# rev1.net
KiCad netlist of a schematic drawn in EAGLE
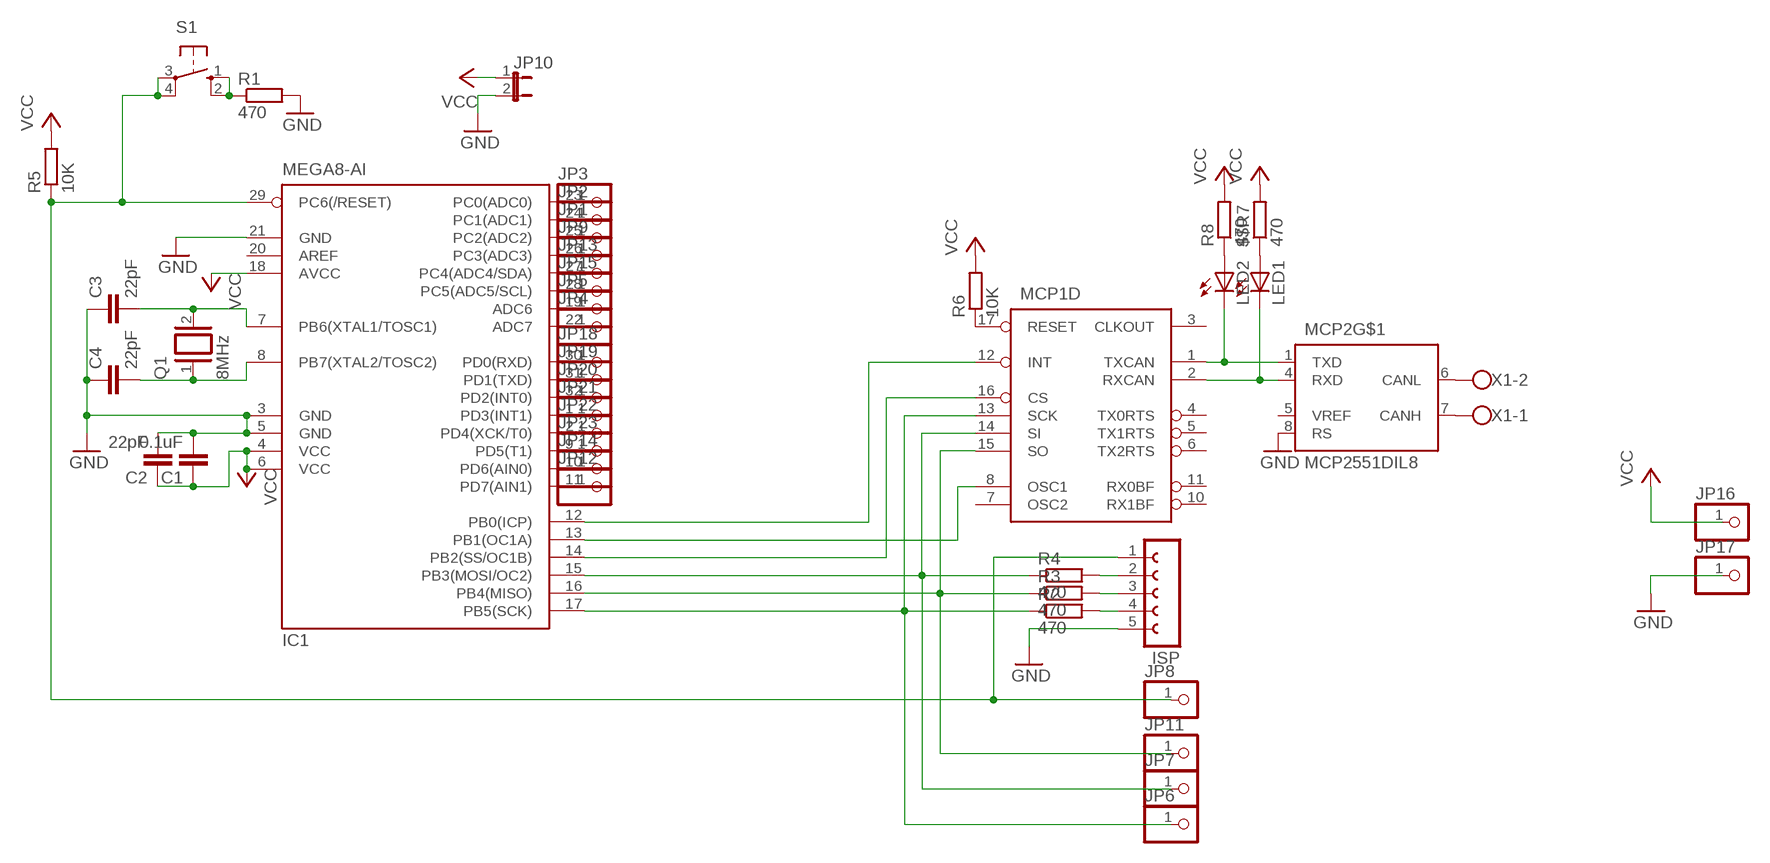
[diagram p0: schematic, sheet 1]

(export (version "E")
  (design (tool "Eeschema 10.0.6"))
  (components
    (comp (ref "$$R7")
      (value "470")
      (footprint "eagle-import:R0603")
      (libsource (lib "eagle-import") (part "R-EU_R0603"))
    )
    (comp (ref "C1")
      (value "0.1uF")
      (footprint "eagle-import:C0603")
      (libsource (lib "eagle-import") (part "C-EUC0603"))
    )
    (comp (ref "C2")
      (value "22pF")
      (footprint "eagle-import:C0603")
      (libsource (lib "eagle-import") (part "C-EUC0603"))
    )
    (comp (ref "C3")
      (value "22pF")
      (footprint "eagle-import:C0603")
      (libsource (lib "eagle-import") (part "C-EUC0603"))
    )
    (comp (ref "C4")
      (value "22pF")
      (footprint "eagle-import:C0603")
      (libsource (lib "eagle-import") (part "C-EUC0603"))
    )
    (comp (ref "IC1")
      (value "MEGA8-AI")
      (footprint "eagle-import:TQFP32-08")
      (fields (field (name "MPN") "ATMEGA8-16AU") (field (name "OC_NEWARK") "unknown"))
      (libsource (lib "eagle-import") (part "MEGA8-AI"))
    )
    (comp (ref "ISP")
      (value "FE05-1")
      (footprint "eagle-import:FE05-1")
      (libsource (lib "eagle-import") (part "FE05-1"))
    )
    (comp (ref "JP1")
      (value "PINHD-1X1")
      (footprint "eagle-import:1X01")
      (libsource (lib "eagle-import") (part "PINHD-1X1"))
    )
    (comp (ref "JP2")
      (value "PINHD-1X1")
      (footprint "eagle-import:1X01")
      (libsource (lib "eagle-import") (part "PINHD-1X1"))
    )
    (comp (ref "JP3")
      (value "PINHD-1X1")
      (footprint "eagle-import:1X01")
      (libsource (lib "eagle-import") (part "PINHD-1X1"))
    )
    (comp (ref "JP4")
      (value "PINHD-1X1")
      (footprint "eagle-import:1X01")
      (libsource (lib "eagle-import") (part "PINHD-1X1"))
    )
    (comp (ref "JP5")
      (value "PINHD-1X1")
      (footprint "eagle-import:1X01")
      (libsource (lib "eagle-import") (part "PINHD-1X1"))
    )
    (comp (ref "JP6")
      (value "PINHD-1X1")
      (footprint "eagle-import:1X01")
      (libsource (lib "eagle-import") (part "PINHD-1X1"))
    )
    (comp (ref "JP7")
      (value "PINHD-1X1")
      (footprint "eagle-import:1X01")
      (libsource (lib "eagle-import") (part "PINHD-1X1"))
    )
    (comp (ref "JP8")
      (value "PINHD-1X1")
      (footprint "eagle-import:1X01")
      (libsource (lib "eagle-import") (part "PINHD-1X1"))
    )
    (comp (ref "JP9")
      (value "PINHD-1X1")
      (footprint "eagle-import:1X01")
      (libsource (lib "eagle-import") (part "PINHD-1X1"))
    )
    (comp (ref "JP10")
      (value "JUMPER-2PTH")
      (footprint "eagle-import:1X02")
      (libsource (lib "eagle-import") (part "JUMPER-2PTH"))
    )
    (comp (ref "JP11")
      (value "PINHD-1X1")
      (footprint "eagle-import:1X01")
      (libsource (lib "eagle-import") (part "PINHD-1X1"))
    )
    (comp (ref "JP12")
      (value "PINHD-1X1")
      (footprint "eagle-import:1X01")
      (libsource (lib "eagle-import") (part "PINHD-1X1"))
    )
    (comp (ref "JP13")
      (value "PINHD-1X1")
      (footprint "eagle-import:1X01")
      (libsource (lib "eagle-import") (part "PINHD-1X1"))
    )
    (comp (ref "JP14")
      (value "PINHD-1X1")
      (footprint "eagle-import:1X01")
      (libsource (lib "eagle-import") (part "PINHD-1X1"))
    )
    (comp (ref "JP15")
      (value "PINHD-1X1")
      (footprint "eagle-import:1X01")
      (libsource (lib "eagle-import") (part "PINHD-1X1"))
    )
    (comp (ref "JP16")
      (value "PINHD-1X1")
      (footprint "eagle-import:1X01")
      (libsource (lib "eagle-import") (part "PINHD-1X1"))
    )
    (comp (ref "JP17")
      (value "PINHD-1X1")
      (footprint "eagle-import:1X01")
      (libsource (lib "eagle-import") (part "PINHD-1X1"))
    )
    (comp (ref "JP18")
      (value "PINHD-1X1")
      (footprint "eagle-import:1X01")
      (libsource (lib "eagle-import") (part "PINHD-1X1"))
    )
    (comp (ref "JP19")
      (value "PINHD-1X1")
      (footprint "eagle-import:1X01")
      (libsource (lib "eagle-import") (part "PINHD-1X1"))
    )
    (comp (ref "JP20")
      (value "PINHD-1X1")
      (footprint "eagle-import:1X01")
      (libsource (lib "eagle-import") (part "PINHD-1X1"))
    )
    (comp (ref "JP21")
      (value "PINHD-1X1")
      (footprint "eagle-import:1X01")
      (libsource (lib "eagle-import") (part "PINHD-1X1"))
    )
    (comp (ref "JP22")
      (value "PINHD-1X1")
      (footprint "eagle-import:1X01")
      (libsource (lib "eagle-import") (part "PINHD-1X1"))
    )
    (comp (ref "JP23")
      (value "PINHD-1X1")
      (footprint "eagle-import:1X01")
      (libsource (lib "eagle-import") (part "PINHD-1X1"))
    )
    (comp (ref "LED1")
      (value "LEDCHIP-LED0603")
      (footprint "eagle-import:CHIP-LED0603")
      (libsource (lib "eagle-import") (part "LEDCHIP-LED0603"))
    )
    (comp (ref "LED2")
      (value "LEDCHIP-LED0603")
      (footprint "eagle-import:CHIP-LED0603")
      (libsource (lib "eagle-import") (part "LEDCHIP-LED0603"))
    )
    (comp (ref "MCP1")
      (value "MCP2515P")
      (footprint "eagle-import:DIL18")
      (libsource (lib "eagle-import") (part "MCP2515P"))
    )
    (comp (ref "MCP2")
      (value "MCP2551DIL8")
      (footprint "eagle-import:DIL08")
      (libsource (lib "eagle-import") (part "MCP2551DIL8"))
    )
    (comp (ref "Q1")
      (value "8MHz")
      (footprint "eagle-import:QS")
      (libsource (lib "eagle-import") (part "XTAL/S"))
    )
    (comp (ref "R1")
      (value "470")
      (footprint "eagle-import:R0603")
      (libsource (lib "eagle-import") (part "R-EU_R0603"))
    )
    (comp (ref "R2")
      (value "470")
      (footprint "eagle-import:R0603")
      (libsource (lib "eagle-import") (part "R-EU_R0603"))
    )
    (comp (ref "R3")
      (value "470")
      (footprint "eagle-import:R0603")
      (libsource (lib "eagle-import") (part "R-EU_R0603"))
    )
    (comp (ref "R4")
      (value "470")
      (footprint "eagle-import:R0603")
      (libsource (lib "eagle-import") (part "R-EU_R0603"))
    )
    (comp (ref "R5")
      (value "10K")
      (footprint "eagle-import:R0603")
      (libsource (lib "eagle-import") (part "R-EU_R0603"))
    )
    (comp (ref "R6")
      (value "10K")
      (footprint "eagle-import:R0603")
      (libsource (lib "eagle-import") (part "R-EU_R0603"))
    )
    (comp (ref "R8")
      (value "470")
      (footprint "eagle-import:R0603")
      (libsource (lib "eagle-import") (part "R-EU_R0603"))
    )
    (comp (ref "S1")
      (value "10-XX")
      (footprint "eagle-import:B3F-10XX")
      (fields (field (name "MPN") "B3F-1000"))
      (libsource (lib "eagle-import") (part "10-XX"))
    )
    (comp (ref "X1")
      (value "W237-102")
      (footprint "eagle-import:W237-102")
      (fields (field (name "MPN") "237-102"))
      (libsource (lib "eagle-import") (part "W237-102"))
    )
  )
  (nets
    (net (code "1") (name "GND") (class "Default")
      (node (ref "C1") (pin "2") (pinfunction "2_2") (pintype "passive"))
      (node (ref "C2") (pin "2") (pinfunction "2_2") (pintype "passive"))
      (node (ref "C3") (pin "1") (pinfunction "1_1") (pintype "passive"))
      (node (ref "C4") (pin "1") (pinfunction "1_1") (pintype "passive"))
      (node (ref "IC1") (pin "21") (pinfunction "GND_21") (pintype "power_in"))
      (node (ref "IC1") (pin "3") (pinfunction "GND_3") (pintype "power_in"))
      (node (ref "IC1") (pin "5") (pinfunction "GND_5") (pintype "power_in"))
      (node (ref "ISP") (pin "5") (pinfunction "5_5") (pintype "passive"))
      (node (ref "JP10") (pin "2") (pinfunction "2_2") (pintype "passive"))
      (node (ref "JP17") (pin "1") (pinfunction "1_1") (pintype "passive"))
      (node (ref "MCP2") (pin "8") (pinfunction "RS_8") (pintype "bidirectional"))
      (node (ref "R1") (pin "2") (pinfunction "2_2") (pintype "passive"))
    )
    (net (code "2") (name "Net-($$R7-Pad1)") (class "Default")
      (node (ref "$$R7") (pin "1") (pinfunction "1_1") (pintype "passive"))
      (node (ref "LED1") (pin "A") (pinfunction "A_A") (pintype "passive"))
    )
    (net (code "3") (name "Net-(IC1-ADC6)") (class "Default")
      (node (ref "IC1") (pin "19") (pinfunction "ADC6_19") (pintype "bidirectional"))
      (node (ref "JP5") (pin "1") (pinfunction "1_1") (pintype "passive"))
    )
    (net (code "4") (name "Net-(IC1-ADC7)") (class "Default")
      (node (ref "IC1") (pin "22") (pinfunction "ADC7_22") (pintype "bidirectional"))
      (node (ref "JP4") (pin "1") (pinfunction "1_1") (pintype "passive"))
    )
    (net (code "5") (name "Net-(IC1-PB0(ICP))") (class "Default")
      (node (ref "IC1") (pin "12") (pinfunction "PB0(ICP)_12") (pintype "bidirectional"))
      (node (ref "MCP1") (pin "12") (pinfunction "INT_12") (pintype "output"))
    )
    (net (code "6") (name "Net-(IC1-PB1(OC1A))") (class "Default")
      (node (ref "IC1") (pin "13") (pinfunction "PB1(OC1A)_13") (pintype "bidirectional"))
      (node (ref "MCP1") (pin "8") (pinfunction "OSC1_8") (pintype "input"))
    )
    (net (code "7") (name "Net-(IC1-PB2(SS{slash}OC1B))") (class "Default")
      (node (ref "IC1") (pin "14") (pinfunction "PB2(SS/OC1B)_14") (pintype "bidirectional"))
      (node (ref "MCP1") (pin "16") (pinfunction "CS_16") (pintype "input"))
    )
    (net (code "8") (name "Net-(IC1-PB3(MOSI{slash}OC2))") (class "Default")
      (node (ref "IC1") (pin "15") (pinfunction "PB3(MOSI/OC2)_15") (pintype "bidirectional"))
      (node (ref "JP7") (pin "1") (pinfunction "1_1") (pintype "passive"))
      (node (ref "MCP1") (pin "14") (pinfunction "SI_14") (pintype "input"))
      (node (ref "R4") (pin "1") (pinfunction "1_1") (pintype "passive"))
    )
    (net (code "9") (name "Net-(IC1-PB4(MISO))") (class "Default")
      (node (ref "IC1") (pin "16") (pinfunction "PB4(MISO)_16") (pintype "bidirectional"))
      (node (ref "JP11") (pin "1") (pinfunction "1_1") (pintype "passive"))
      (node (ref "MCP1") (pin "15") (pinfunction "SO_15") (pintype "output"))
      (node (ref "R3") (pin "1") (pinfunction "1_1") (pintype "passive"))
    )
    (net (code "10") (name "Net-(IC1-PB5(SCK))") (class "Default")
      (node (ref "IC1") (pin "17") (pinfunction "PB5(SCK)_17") (pintype "bidirectional"))
      (node (ref "JP6") (pin "1") (pinfunction "1_1") (pintype "passive"))
      (node (ref "MCP1") (pin "13") (pinfunction "SCK_13") (pintype "input"))
      (node (ref "R2") (pin "1") (pinfunction "1_1") (pintype "passive"))
    )
    (net (code "11") (name "Net-(IC1-PB6(XTAL1{slash}TOSC1))") (class "Default")
      (node (ref "C3") (pin "2") (pinfunction "2_2") (pintype "passive"))
      (node (ref "IC1") (pin "7") (pinfunction "PB6(XTAL1/TOSC1)_7") (pintype "bidirectional"))
      (node (ref "Q1") (pin "2") (pinfunction "2_2") (pintype "passive"))
    )
    (net (code "12") (name "Net-(IC1-PB7(XTAL2{slash}TOSC2))") (class "Default")
      (node (ref "C4") (pin "2") (pinfunction "2_2") (pintype "passive"))
      (node (ref "IC1") (pin "8") (pinfunction "PB7(XTAL2/TOSC2)_8") (pintype "bidirectional"))
      (node (ref "Q1") (pin "1") (pinfunction "1_1") (pintype "passive"))
    )
    (net (code "13") (name "Net-(IC1-PC0(ADC0))") (class "Default")
      (node (ref "IC1") (pin "23") (pinfunction "PC0(ADC0)_23") (pintype "bidirectional"))
      (node (ref "JP3") (pin "1") (pinfunction "1_1") (pintype "passive"))
    )
    (net (code "14") (name "Net-(IC1-PC1(ADC1))") (class "Default")
      (node (ref "IC1") (pin "24") (pinfunction "PC1(ADC1)_24") (pintype "bidirectional"))
      (node (ref "JP2") (pin "1") (pinfunction "1_1") (pintype "passive"))
    )
    (net (code "15") (name "Net-(IC1-PC2(ADC2))") (class "Default")
      (node (ref "IC1") (pin "25") (pinfunction "PC2(ADC2)_25") (pintype "bidirectional"))
      (node (ref "JP1") (pin "1") (pinfunction "1_1") (pintype "passive"))
    )
    (net (code "16") (name "Net-(IC1-PC3(ADC3))") (class "Default")
      (node (ref "IC1") (pin "26") (pinfunction "PC3(ADC3)_26") (pintype "bidirectional"))
      (node (ref "JP9") (pin "1") (pinfunction "1_1") (pintype "passive"))
    )
    (net (code "17") (name "Net-(IC1-PC4(ADC4{slash}SDA))") (class "Default")
      (node (ref "IC1") (pin "27") (pinfunction "PC4(ADC4/SDA)_27") (pintype "bidirectional"))
      (node (ref "JP13") (pin "1") (pinfunction "1_1") (pintype "passive"))
    )
    (net (code "18") (name "Net-(IC1-PC5(ADC5{slash}SCL))") (class "Default")
      (node (ref "IC1") (pin "28") (pinfunction "PC5(ADC5/SCL)_28") (pintype "bidirectional"))
      (node (ref "JP15") (pin "1") (pinfunction "1_1") (pintype "passive"))
    )
    (net (code "19") (name "Net-(IC1-PC6({slash}RESET))") (class "Default")
      (node (ref "IC1") (pin "29") (pinfunction "PC6(/RESET)_29") (pintype "bidirectional"))
      (node (ref "ISP") (pin "1") (pinfunction "1_1") (pintype "passive"))
      (node (ref "JP8") (pin "1") (pinfunction "1_1") (pintype "passive"))
      (node (ref "R5") (pin "1") (pinfunction "1_1") (pintype "passive"))
      (node (ref "S1") (pin "3") (pinfunction "P_3") (pintype "passive"))
      (node (ref "S1") (pin "4") (pinfunction "P1_4") (pintype "passive"))
    )
    (net (code "20") (name "Net-(IC1-PD0(RXD))") (class "Default")
      (node (ref "IC1") (pin "30") (pinfunction "PD0(RXD)_30") (pintype "bidirectional"))
      (node (ref "JP18") (pin "1") (pinfunction "1_1") (pintype "passive"))
    )
    (net (code "21") (name "Net-(IC1-PD1(TXD))") (class "Default")
      (node (ref "IC1") (pin "31") (pinfunction "PD1(TXD)_31") (pintype "bidirectional"))
      (node (ref "JP19") (pin "1") (pinfunction "1_1") (pintype "passive"))
    )
    (net (code "22") (name "Net-(IC1-PD2(INT0))") (class "Default")
      (node (ref "IC1") (pin "32") (pinfunction "PD2(INT0)_32") (pintype "bidirectional"))
      (node (ref "JP20") (pin "1") (pinfunction "1_1") (pintype "passive"))
    )
    (net (code "23") (name "Net-(IC1-PD3(INT1))") (class "Default")
      (node (ref "IC1") (pin "1") (pinfunction "PD3(INT1)_1") (pintype "bidirectional"))
      (node (ref "JP21") (pin "1") (pinfunction "1_1") (pintype "passive"))
    )
    (net (code "24") (name "Net-(IC1-PD4(XCK{slash}T0))") (class "Default")
      (node (ref "IC1") (pin "2") (pinfunction "PD4(XCK/T0)_2") (pintype "bidirectional"))
      (node (ref "JP22") (pin "1") (pinfunction "1_1") (pintype "passive"))
    )
    (net (code "25") (name "Net-(IC1-PD5(T1))") (class "Default")
      (node (ref "IC1") (pin "9") (pinfunction "PD5(T1)_9") (pintype "bidirectional"))
      (node (ref "JP23") (pin "1") (pinfunction "1_1") (pintype "passive"))
    )
    (net (code "26") (name "Net-(IC1-PD6(AIN0))") (class "Default")
      (node (ref "IC1") (pin "10") (pinfunction "PD6(AIN0)_10") (pintype "bidirectional"))
      (node (ref "JP14") (pin "1") (pinfunction "1_1") (pintype "passive"))
    )
    (net (code "27") (name "Net-(IC1-PD7(AIN1))") (class "Default")
      (node (ref "IC1") (pin "11") (pinfunction "PD7(AIN1)_11") (pintype "bidirectional"))
      (node (ref "JP12") (pin "1") (pinfunction "1_1") (pintype "passive"))
    )
    (net (code "28") (name "Net-(ISP-Pad2)") (class "Default")
      (node (ref "ISP") (pin "2") (pinfunction "2_2") (pintype "passive"))
      (node (ref "R4") (pin "2") (pinfunction "2_2") (pintype "passive"))
    )
    (net (code "29") (name "Net-(ISP-Pad3)") (class "Default")
      (node (ref "ISP") (pin "3") (pinfunction "3_3") (pintype "passive"))
      (node (ref "R3") (pin "2") (pinfunction "2_2") (pintype "passive"))
    )
    (net (code "30") (name "Net-(ISP-Pad4)") (class "Default")
      (node (ref "ISP") (pin "4") (pinfunction "4_4") (pintype "passive"))
      (node (ref "R2") (pin "2") (pinfunction "2_2") (pintype "passive"))
    )
    (net (code "31") (name "Net-(LED2-PadA)") (class "Default")
      (node (ref "LED2") (pin "A") (pinfunction "A_A") (pintype "passive"))
      (node (ref "R8") (pin "1") (pinfunction "1_1") (pintype "passive"))
    )
    (net (code "32") (name "Net-(MCP1A-RESET)") (class "Default")
      (node (ref "MCP1") (pin "17") (pinfunction "RESET_17") (pintype "input"))
      (node (ref "R6") (pin "1") (pinfunction "1_1") (pintype "passive"))
    )
    (net (code "33") (name "Net-(MCP1A-RXCAN)") (class "Default")
      (node (ref "LED1") (pin "C") (pinfunction "C_C") (pintype "passive"))
      (node (ref "MCP1") (pin "2") (pinfunction "RXCAN_2") (pintype "input"))
      (node (ref "MCP2") (pin "4") (pinfunction "RXD_4") (pintype "bidirectional"))
    )
    (net (code "34") (name "Net-(MCP1A-TXCAN)") (class "Default")
      (node (ref "LED2") (pin "C") (pinfunction "C_C") (pintype "passive"))
      (node (ref "MCP1") (pin "1") (pinfunction "TXCAN_1") (pintype "output"))
      (node (ref "MCP2") (pin "1") (pinfunction "TXD_1") (pintype "bidirectional"))
    )
    (net (code "35") (name "Net-(MCP2A-CANH)") (class "Default")
      (node (ref "MCP2") (pin "7") (pinfunction "CANH_7") (pintype "bidirectional"))
      (node (ref "X1") (pin "1") (pinfunction "KL_1") (pintype "passive"))
    )
    (net (code "36") (name "Net-(MCP2A-CANL)") (class "Default")
      (node (ref "MCP2") (pin "6") (pinfunction "CANL_6") (pintype "bidirectional"))
      (node (ref "X1") (pin "2") (pinfunction "KL_2") (pintype "passive"))
    )
    (net (code "37") (name "Net-(S1-S)") (class "Default")
      (node (ref "R1") (pin "1") (pinfunction "1_1") (pintype "passive"))
      (node (ref "S1") (pin "1") (pinfunction "S_1") (pintype "passive"))
      (node (ref "S1") (pin "2") (pinfunction "S1_2") (pintype "passive"))
    )
    (net (code "38") (name "VCC") (class "Default")
      (node (ref "$$R7") (pin "2") (pinfunction "2_2") (pintype "passive"))
      (node (ref "C1") (pin "1") (pinfunction "1_1") (pintype "passive"))
      (node (ref "C2") (pin "1") (pinfunction "1_1") (pintype "passive"))
      (node (ref "IC1") (pin "18") (pinfunction "AVCC_18") (pintype "power_in"))
      (node (ref "IC1") (pin "4") (pinfunction "VCC_4") (pintype "power_in"))
      (node (ref "IC1") (pin "6") (pinfunction "VCC_6") (pintype "power_in"))
      (node (ref "JP10") (pin "1") (pinfunction "1_1") (pintype "passive"))
      (node (ref "JP16") (pin "1") (pinfunction "1_1") (pintype "passive"))
      (node (ref "R5") (pin "2") (pinfunction "2_2") (pintype "passive"))
      (node (ref "R6") (pin "2") (pinfunction "2_2") (pintype "passive"))
      (node (ref "R8") (pin "2") (pinfunction "2_2") (pintype "passive"))
    )
    (net (code "39") (name "unconnected-(IC1-AREF-Pad20)") (class "Default")
      (node (ref "IC1") (pin "20") (pinfunction "AREF_20") (pintype "passive"))
    )
    (net (code "40") (name "unconnected-(MCP1A-CLKOUT-Pad3)") (class "Default")
      (node (ref "MCP1") (pin "3") (pinfunction "CLKOUT_3") (pintype "output"))
    )
    (net (code "41") (name "unconnected-(MCP1A-OSC2-Pad7)") (class "Default")
      (node (ref "MCP1") (pin "7") (pinfunction "OSC2_7") (pintype "input"))
    )
    (net (code "42") (name "unconnected-(MCP1A-RX0BF-Pad11)") (class "Default")
      (node (ref "MCP1") (pin "11") (pinfunction "RX0BF_11") (pintype "output"))
    )
    (net (code "43") (name "unconnected-(MCP1A-RX1BF-Pad10)") (class "Default")
      (node (ref "MCP1") (pin "10") (pinfunction "RX1BF_10") (pintype "output"))
    )
    (net (code "44") (name "unconnected-(MCP1A-TX0RTS-Pad4)") (class "Default")
      (node (ref "MCP1") (pin "4") (pinfunction "TX0RTS_4") (pintype "input"))
    )
    (net (code "45") (name "unconnected-(MCP1A-TX1RTS-Pad5)") (class "Default")
      (node (ref "MCP1") (pin "5") (pinfunction "TX1RTS_5") (pintype "input"))
    )
    (net (code "46") (name "unconnected-(MCP1A-TX2RTS-Pad6)") (class "Default")
      (node (ref "MCP1") (pin "6") (pinfunction "TX2RTS_6") (pintype "input"))
    )
    (net (code "47") (name "unconnected-(MCP2A-VREF-Pad5)") (class "Default")
      (node (ref "MCP2") (pin "5") (pinfunction "VREF_5") (pintype "bidirectional"))
    )
  )
)
